# flora_vibe.net
KiCad netlist of a schematic drawn in EAGLE
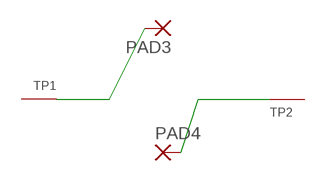
[diagram p0: schematic, sheet 1]

(export (version "E")
  (design (tool "Eeschema 10.0.6"))
  (components
    (comp (ref "PAD3")
      (value "2,54/1,0")
      (footprint "eagle-import:2,54_1,0")
      (libsource (lib "eagle-import") (part "2,54/1,0"))
    )
    (comp (ref "PAD4")
      (value "2,54/1,0")
      (footprint "eagle-import:2,54_1,0")
      (libsource (lib "eagle-import") (part "2,54/1,0"))
    )
    (comp (ref "TP1")
      (value "SEWTAP0.4IN")
      (footprint "eagle-import:SEWINGTAP_0.4")
      (libsource (lib "eagle-import") (part "SEWTAP0.4IN"))
    )
    (comp (ref "TP2")
      (value "SEWTAP0.4IN")
      (footprint "eagle-import:SEWINGTAP_0.4")
      (libsource (lib "eagle-import") (part "SEWTAP0.4IN"))
    )
  )
  (nets
    (net (code "1") (name "Net-(PAD3-P)") (class "Default")
      (node (ref "PAD3") (pin "1") (pinfunction "P_1") (pintype "passive"))
      (node (ref "TP1") (pin "TAP") (pinfunction "SEW_TAP") (pintype "bidirectional"))
    )
    (net (code "2") (name "Net-(PAD4-P)") (class "Default")
      (node (ref "PAD4") (pin "1") (pinfunction "P_1") (pintype "passive"))
      (node (ref "TP2") (pin "TAP") (pinfunction "SEW_TAP") (pintype "bidirectional"))
    )
  )
)
